# WIFI.net
KiCad netlist of a schematic drawn in Altium Designer
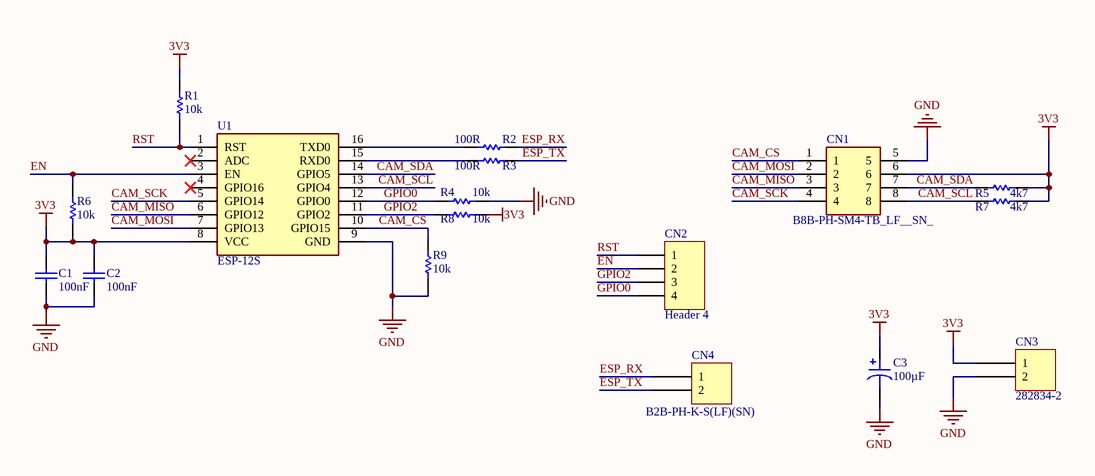
[diagram p0: WIFI.SchDoc]

(export (version "E")
  (design (tool "Eeschema 10.0.6"))
  (components
    (comp (ref "C1")
      (value "100nF")
      (footprint "1608[0603]")
      (description "Capacitor")
      (fields (field (name "Comment") "Cap") (field (name "PUBLISHER") "Altium Limited"))
      (libsource (lib "Miscellaneous Devices") (part "Cap"))
    )
    (comp (ref "C2")
      (value "100nF")
      (footprint "1608[0603]")
      (description "Capacitor")
      (fields (field (name "Comment") "Cap") (field (name "PUBLISHER") "Altium Limited"))
      (libsource (lib "Miscellaneous Devices") (part "Cap"))
    )
    (comp (ref "C3")
      (value "100µF")
      (footprint "CAP ALSMD POLY 5.3MM H6.0MM")
      (description "CAP ALUM POLY 100UF 20% 6.3V SMD")
      (fields
        (field (name "PART NUMBER") "6SVPC100M")
        (field (name "MANUFACTURER") "Panasonic Electronic Components")
      )
      (libsource (lib "Celestial Altium Library - altium_library") (part "Polarised Capacitor"))
    )
    (comp (ref "CN1")
      (value "B8B-PH-SM4-TB_LF__SN_")
      (footprint "SamacSys:B8B-PH-SM4-TB")
      (description "Connector")
      (fields (field (name "MANUFACTURER_PART_NUMBER") "B8B-PH-SM4-TB(LF)(SN)"))
      (libsource (lib "*") (part "B8B-PH-SM4-TB_LF__SN_"))
    )
    (comp (ref "CN2")
      (value "Header 4")
      (footprint "HDR1X4")
      (description "Header, 4-Pin")
      (fields (field (name "PUBLISHER") "Altium Limited"))
      (libsource (lib "Miscellaneous Connectors") (part "Header 4"))
    )
    (comp (ref "CN3")
      (value "282834-2")
      (footprint "TE 282834-2")
      (description "TERM BLK 2P SIDE ENT 2.54MM PCB")
      (fields (field (name "MANUFACTURER") "TE Connectivity AMP Connectors") (field (name "VOLTAGE") "150V"))
      (libsource (lib "Celestial Altium Library - altium_library") (part "2 Pin"))
    )
    (comp (ref "CN4")
      (value "B2B-PH-K-S(LF)(SN)")
      (footprint "JST B2B-PH-K")
      (description "CONN HEADER VERT 2POS 2MM")
      (fields (field (name "MANUFACTURER") "JST Sales America Inc."))
      (libsource (lib "Celestial Altium Library - altium_library") (part "2 Pin"))
    )
    (comp (ref "R1")
      (value "10k")
      (footprint "1608[0603]")
      (description "Resistor")
      (fields (field (name "Comment") "Res1") (field (name "PUBLISHER") "Altium Limited"))
      (libsource (lib "Miscellaneous Devices") (part "Res1"))
    )
    (comp (ref "R2")
      (value "100R")
      (footprint "1608[0603]")
      (description "Resistor")
      (fields (field (name "Comment") "Res1") (field (name "PUBLISHER") "Altium Limited"))
      (libsource (lib "Miscellaneous Devices") (part "Res1"))
    )
    (comp (ref "R3")
      (value "100R")
      (footprint "1608[0603]")
      (description "Resistor")
      (fields (field (name "Comment") "Res1") (field (name "PUBLISHER") "Altium Limited"))
      (libsource (lib "Miscellaneous Devices") (part "Res1"))
    )
    (comp (ref "R4")
      (value "10k")
      (footprint "1608[0603]")
      (description "Resistor")
      (fields (field (name "Comment") "Res1") (field (name "PUBLISHER") "Altium Limited"))
      (libsource (lib "Miscellaneous Devices") (part "Res1"))
    )
    (comp (ref "R5")
      (value "4k7")
      (footprint "1608[0603]")
      (description "Resistor")
      (fields (field (name "Comment") "Res1") (field (name "PUBLISHER") "Altium Limited"))
      (libsource (lib "Miscellaneous Devices") (part "Res1"))
    )
    (comp (ref "R6")
      (value "10k")
      (footprint "1608[0603]")
      (description "Resistor")
      (fields (field (name "Comment") "Res1") (field (name "PUBLISHER") "Altium Limited"))
      (libsource (lib "Miscellaneous Devices") (part "Res1"))
    )
    (comp (ref "R7")
      (value "4k7")
      (footprint "1608[0603]")
      (description "Resistor")
      (fields (field (name "Comment") "Res1") (field (name "PUBLISHER") "Altium Limited"))
      (libsource (lib "Miscellaneous Devices") (part "Res1"))
    )
    (comp (ref "R8")
      (value "10k")
      (footprint "1608[0603]")
      (description "Resistor")
      (fields (field (name "Comment") "Res1") (field (name "PUBLISHER") "Altium Limited"))
      (libsource (lib "Miscellaneous Devices") (part "Res1"))
    )
    (comp (ref "R9")
      (value "10k")
      (footprint "1608[0603]")
      (description "Resistor")
      (fields (field (name "Comment") "Res1") (field (name "PUBLISHER") "Altium Limited"))
      (libsource (lib "Miscellaneous Devices") (part "Res1"))
    )
    (comp (ref "U1")
      (value "ESP-12S")
      (footprint "SamacSys:ESP12S")
      (description "Integrated Circuit")
      (fields (field (name "MOUSER PART NUMBER") "223-ESP-12S"))
      (libsource (lib "*") (part "ESP-12S"))
    )
  )
  (nets
    (net (code "1") (name "/CAM_CS") (class "Default")
      (node (ref "CN1") (pin "1") (pinfunction "1_1") (pintype "passive"))
      (node (ref "R9") (pin "1") (pinfunction "1_1") (pintype "passive"))
      (node (ref "U1") (pin "10") (pinfunction "GPIO15_10") (pintype "passive"))
    )
    (net (code "2") (name "/CAM_MISO") (class "Default")
      (node (ref "CN1") (pin "3") (pinfunction "3_3") (pintype "passive"))
      (node (ref "U1") (pin "6") (pinfunction "GPIO12_6") (pintype "passive"))
    )
    (net (code "3") (name "/CAM_MOSI") (class "Default")
      (node (ref "CN1") (pin "2") (pinfunction "2_2") (pintype "passive"))
      (node (ref "U1") (pin "7") (pinfunction "GPIO13_7") (pintype "passive"))
    )
    (net (code "4") (name "/CAM_SCK") (class "Default")
      (node (ref "CN1") (pin "4") (pinfunction "4_4") (pintype "passive"))
      (node (ref "U1") (pin "5") (pinfunction "GPIO14_5") (pintype "passive"))
    )
    (net (code "5") (name "/CAM_SCL") (class "Default")
      (node (ref "CN1") (pin "8") (pinfunction "8_8") (pintype "passive"))
      (node (ref "R7") (pin "1") (pinfunction "1_1") (pintype "passive"))
      (node (ref "U1") (pin "13") (pinfunction "GPIO4_13") (pintype "passive"))
    )
    (net (code "6") (name "/CAM_SDA") (class "Default")
      (node (ref "CN1") (pin "7") (pinfunction "7_7") (pintype "passive"))
      (node (ref "R5") (pin "1") (pinfunction "1_1") (pintype "passive"))
      (node (ref "U1") (pin "14") (pinfunction "GPIO5_14") (pintype "passive"))
    )
    (net (code "7") (name "/EN") (class "Default")
      (node (ref "CN2") (pin "2") (pinfunction "2_2") (pintype "passive"))
      (node (ref "R6") (pin "1") (pinfunction "1_1") (pintype "passive"))
      (node (ref "U1") (pin "3") (pinfunction "EN_3") (pintype "passive"))
    )
    (net (code "8") (name "/ESP_RX") (class "Default")
      (node (ref "CN4") (pin "1") (pinfunction "1_1") (pintype "passive"))
      (node (ref "R2") (pin "1") (pinfunction "1_1") (pintype "passive"))
    )
    (net (code "9") (name "/ESP_TX") (class "Default")
      (node (ref "CN4") (pin "2") (pinfunction "2_2") (pintype "passive"))
      (node (ref "R3") (pin "1") (pinfunction "1_1") (pintype "passive"))
    )
    (net (code "10") (name "/GPIO0") (class "Default")
      (node (ref "CN2") (pin "4") (pinfunction "4_4") (pintype "passive"))
      (node (ref "R4") (pin "1") (pinfunction "1_1") (pintype "passive"))
      (node (ref "U1") (pin "12") (pinfunction "GPIO0_12") (pintype "passive"))
    )
    (net (code "11") (name "/GPIO2") (class "Default")
      (node (ref "CN2") (pin "3") (pinfunction "3_3") (pintype "passive"))
      (node (ref "R8") (pin "1") (pinfunction "1_1") (pintype "passive"))
      (node (ref "U1") (pin "11") (pinfunction "GPIO2_11") (pintype "passive"))
    )
    (net (code "12") (name "/RST") (class "Default")
      (node (ref "CN2") (pin "1") (pinfunction "1_1") (pintype "passive"))
      (node (ref "R1") (pin "1") (pinfunction "1_1") (pintype "passive"))
      (node (ref "U1") (pin "1") (pinfunction "RST_1") (pintype "passive"))
    )
    (net (code "13") (name "3V3") (class "Default")
      (node (ref "C1") (pin "1") (pinfunction "1_1") (pintype "passive"))
      (node (ref "C2") (pin "1") (pinfunction "1_1") (pintype "passive"))
      (node (ref "C3") (pin "1") (pinfunction "1_1") (pintype "passive"))
      (node (ref "CN1") (pin "6") (pinfunction "6_6") (pintype "passive"))
      (node (ref "CN3") (pin "1") (pinfunction "1_1") (pintype "passive"))
      (node (ref "R1") (pin "2") (pinfunction "2_2") (pintype "passive"))
      (node (ref "R5") (pin "2") (pinfunction "2_2") (pintype "passive"))
      (node (ref "R6") (pin "2") (pinfunction "2_2") (pintype "passive"))
      (node (ref "R7") (pin "2") (pinfunction "2_2") (pintype "passive"))
      (node (ref "R8") (pin "2") (pinfunction "2_2") (pintype "passive"))
      (node (ref "U1") (pin "8") (pinfunction "VCC_8") (pintype "passive"))
    )
    (net (code "14") (name "GND") (class "Default")
      (node (ref "C1") (pin "2") (pinfunction "2_2") (pintype "passive"))
      (node (ref "C2") (pin "2") (pinfunction "2_2") (pintype "passive"))
      (node (ref "C3") (pin "2") (pinfunction "2_2") (pintype "passive"))
      (node (ref "CN1") (pin "5") (pinfunction "5_5") (pintype "passive"))
      (node (ref "CN3") (pin "2") (pinfunction "2_2") (pintype "passive"))
      (node (ref "R4") (pin "2") (pinfunction "2_2") (pintype "passive"))
      (node (ref "R9") (pin "2") (pinfunction "2_2") (pintype "passive"))
      (node (ref "U1") (pin "9") (pinfunction "GND_9") (pintype "passive"))
    )
    (net (code "15") (name "Net-(U1-RXD0)") (class "Default")
      (node (ref "R3") (pin "2") (pinfunction "2_2") (pintype "passive"))
      (node (ref "U1") (pin "15") (pinfunction "RXD0_15") (pintype "passive"))
    )
    (net (code "16") (name "Net-(U1-TXD0)") (class "Default")
      (node (ref "R2") (pin "2") (pinfunction "2_2") (pintype "passive"))
      (node (ref "U1") (pin "16") (pinfunction "TXD0_16") (pintype "passive"))
    )
    (net (code "17") (name "unconnected-(U1-ADC-Pad2)") (class "Default")
      (node (ref "U1") (pin "2") (pinfunction "ADC_2") (pintype "passive+no_connect"))
    )
    (net (code "18") (name "unconnected-(U1-GPIO16-Pad4)") (class "Default")
      (node (ref "U1") (pin "4") (pinfunction "GPIO16_4") (pintype "passive+no_connect"))
    )
  )
)
